# cpu.net
KiCad netlist of a schematic drawn in Altium Designer
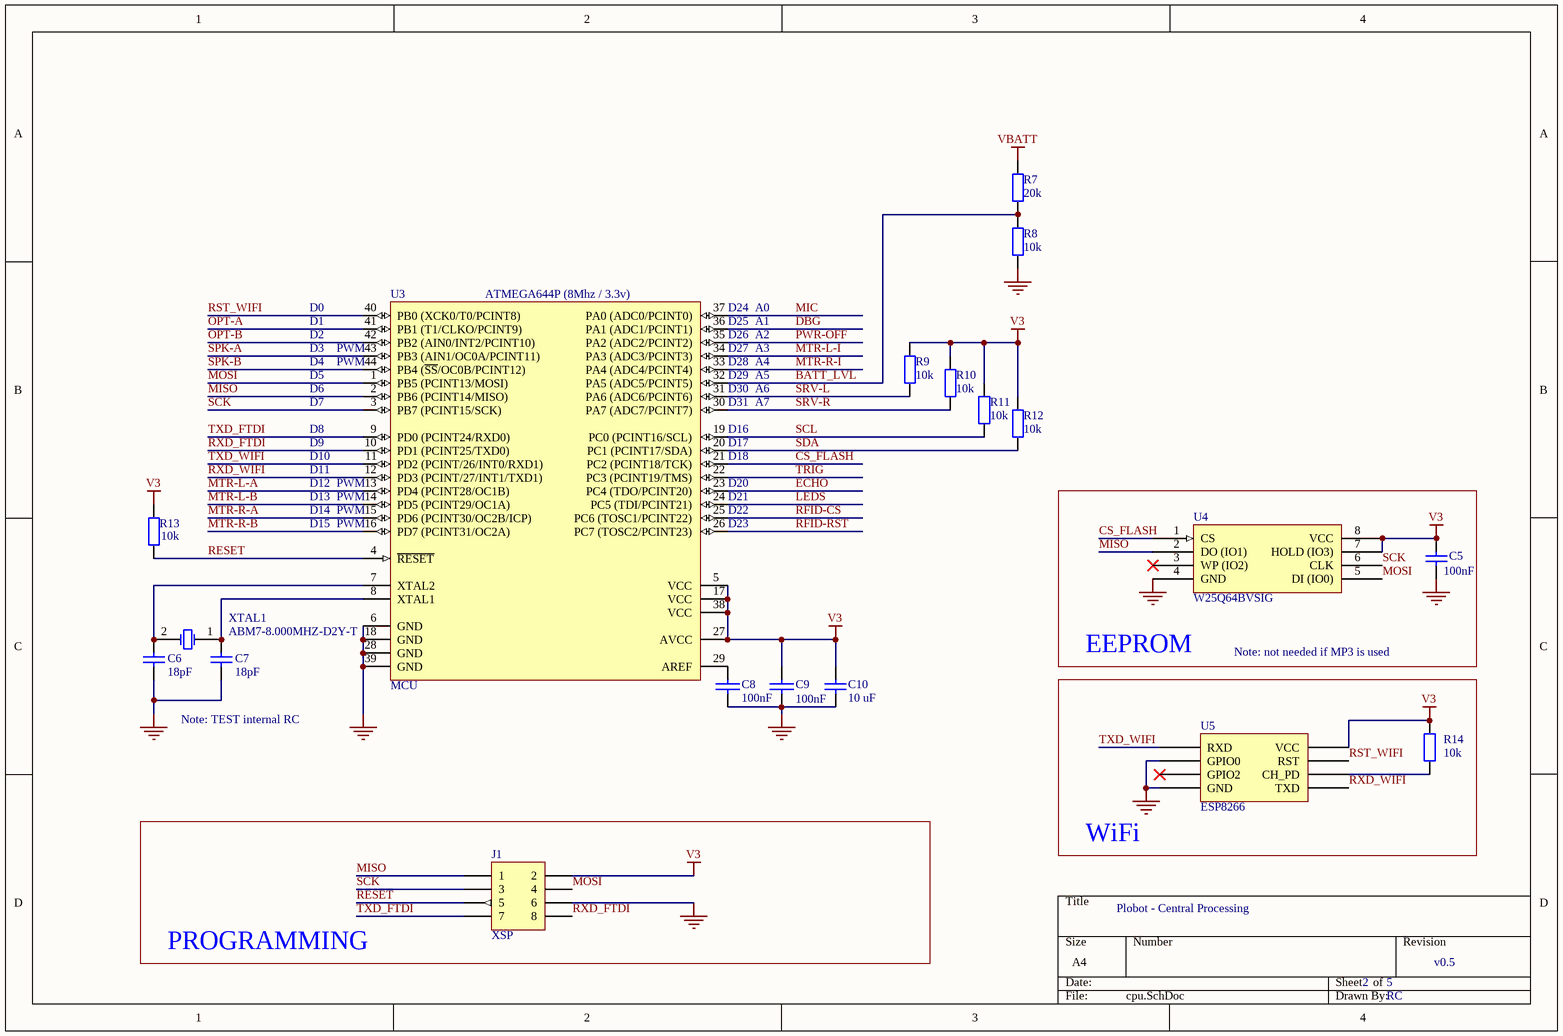
[diagram p0: cpu.SchDoc]

(export (version "E")
  (design (tool "Eeschema 10.0.6"))
  (components
    (comp (ref "C5")
      (value "100nF")
      (footprint "plobot_review:CAPC1608N")
      (description "Capacitor")
      (fields (field (name "PUBLISHER") "Altium Limited"))
      (libsource (lib "*") (part "Cap"))
    )
    (comp (ref "C6")
      (value "18pF")
      (footprint "plobot_review:CAPC1608N")
      (description "Capacitor")
      (fields (field (name "PUBLISHER") "Altium Limited"))
      (libsource (lib "*") (part "Cap"))
    )
    (comp (ref "C7")
      (value "18pF")
      (footprint "plobot_review:CAPC1608N")
      (description "Capacitor")
      (fields (field (name "PUBLISHER") "Altium Limited"))
      (libsource (lib "*") (part "Cap"))
    )
    (comp (ref "C8")
      (value "100nF")
      (footprint "plobot_review:CAPC1608N")
      (description "Capacitor")
      (libsource (lib "*") (part "CAP"))
    )
    (comp (ref "C9")
      (value "100nF")
      (footprint "plobot_review:CAPC1608N")
      (description "Capacitor")
      (libsource (lib "*") (part "CAP"))
    )
    (comp (ref "C10")
      (value "10 uF")
      (footprint "plobot_review:CAPC3216N")
      (description "Capacitor")
      (fields (field (name "PUBLISHER") "Altium Limited"))
      (libsource (lib "main_pcb") (part "Cap_2"))
    )
    (comp (ref "J1")
      (value "XSP")
      (footprint "plobot_review:HDR2X4H")
      (description "Header, 4-Pin, Dual row, Right Angle")
      (fields (field (name "PUBLISHER") "Altium Limited"))
      (libsource (lib "Miscellaneous Connectors") (part "Header 4X2H"))
    )
    (comp (ref "R7")
      (value "20k")
      (footprint "plobot_review:RESC1608N")
      (description "Resistor")
      (fields (field (name "PUBLISHER") "Altium Limited"))
      (libsource (lib "") (part "Res2_1"))
    )
    (comp (ref "R8")
      (value "10k")
      (footprint "plobot_review:RESC1608N")
      (description "Resistor")
      (fields (field (name "PUBLISHER") "Altium Limited"))
      (libsource (lib "") (part "Res2_1"))
    )
    (comp (ref "R9")
      (value "10k")
      (footprint "plobot_review:RESC1608N")
      (description "Resistor")
      (fields (field (name "PUBLISHER") "Altium Limited"))
      (libsource (lib "*") (part "Res2"))
    )
    (comp (ref "R10")
      (value "10k")
      (footprint "plobot_review:RESC1608N")
      (description "Resistor")
      (fields (field (name "PUBLISHER") "Altium Limited"))
      (libsource (lib "*") (part "Res2"))
    )
    (comp (ref "R11")
      (value "10k")
      (footprint "plobot_review:RESC1608N")
      (description "Resistor")
      (fields (field (name "PUBLISHER") "Altium Limited"))
      (libsource (lib "") (part "Res2_1"))
    )
    (comp (ref "R12")
      (value "10k")
      (footprint "plobot_review:RESC1608N")
      (description "Resistor")
      (fields (field (name "PUBLISHER") "Altium Limited"))
      (libsource (lib "*") (part "Res2"))
    )
    (comp (ref "R13")
      (value "10k")
      (footprint "plobot_review:RESC1608N")
      (description "Resistor")
      (fields (field (name "PUBLISHER") "Altium Limited"))
      (libsource (lib "*") (part "Res2"))
    )
    (comp (ref "R14")
      (value "10k")
      (footprint "plobot_review:RESC1608N")
      (description "Resistor")
      (fields (field (name "PUBLISHER") "Altium Limited"))
      (libsource (lib "") (part "Res2_2"))
    )
    (comp (ref "U3")
      (value "MCU")
      (footprint "plobot_review:atmega644p")
      (description "8-bit AVR Microcontroller, 2.7-5.5V, 20MHz, 64KB Flash, 2KB EEPROM, 4KB SRAM, 44-pin TQFP")
      (libsource (lib "*") (part "ATmega644-20AU"))
    )
    (comp (ref "U4")
      (value "W25Q64BVSIG")
      (footprint "plobot_review:W25Q64BVSIG")
      (libsource (lib "components") (part "W25Q64BVSIG"))
    )
    (comp (ref "U5")
      (value "ESP8266")
      (footprint "plobot_review:ESP8266")
      (libsource (lib "components") (part "ESP8266"))
    )
    (comp (ref "XTAL1")
      (value "ABM7-8.000MHZ-D2Y-T")
      (footprint "plobot_review:XTAL")
      (libsource (lib "components") (part "ABM7-8.000MHZ-D2Y-T"))
    )
  )
  (nets
    (net (code "1") (name "/BATT_LVL") (class "Default")
      (node (ref "R7") (pin "1") (pinfunction "1_1") (pintype "passive"))
      (node (ref "R8") (pin "2") (pinfunction "2_2") (pintype "passive"))
      (node (ref "U3") (pin "32") (pinfunction "PA5_(ADC5/PCINT5)_32") (pintype "bidirectional"))
    )
    (net (code "2") (name "/CS_FLASH") (class "Default")
      (node (ref "U3") (pin "21") (pinfunction "PC2_(PCINT18/TCK)_21") (pintype "bidirectional"))
      (node (ref "U4") (pin "1") (pinfunction "CS_1") (pintype "input"))
    )
    (net (code "3") (name "/DBG") (class "Default")
      (node (ref "U3") (pin "36") (pinfunction "PA1_(ADC1/PCINT1)_36") (pintype "bidirectional"))
    )
    (net (code "4") (name "/ECHO") (class "Default")
      (node (ref "U3") (pin "23") (pinfunction "PC4_(TDO/PCINT20)_23") (pintype "bidirectional"))
    )
    (net (code "5") (name "/LEDS") (class "Default")
      (node (ref "U3") (pin "24") (pinfunction "PC5_(TDI/PCINT21)_24") (pintype "bidirectional"))
    )
    (net (code "6") (name "/MIC") (class "Default")
      (node (ref "U3") (pin "37") (pinfunction "PA0_(ADC0/PCINT0)_37") (pintype "bidirectional"))
    )
    (net (code "7") (name "/MISO") (class "Default")
      (node (ref "J1") (pin "1") (pinfunction "1_1") (pintype "passive"))
      (node (ref "U3") (pin "2") (pinfunction "PB6_(PCINT14/MISO)_2") (pintype "bidirectional"))
      (node (ref "U4") (pin "2") (pinfunction "DO_(IO1)_2") (pintype "passive"))
    )
    (net (code "8") (name "/MOSI") (class "Default")
      (node (ref "J1") (pin "4") (pinfunction "4_4") (pintype "passive"))
      (node (ref "U3") (pin "1") (pinfunction "PB5_(PCINT13/MOSI)_1") (pintype "bidirectional"))
      (node (ref "U4") (pin "5") (pinfunction "DI_(IO0)_5") (pintype "passive"))
    )
    (net (code "9") (name "/MTR-L-A") (class "Default")
      (node (ref "U3") (pin "13") (pinfunction "PD4_(PCINT28/OC1B)_13") (pintype "bidirectional"))
    )
    (net (code "10") (name "/MTR-L-B") (class "Default")
      (node (ref "U3") (pin "14") (pinfunction "PD5_(PCINT29/OC1A)_14") (pintype "bidirectional"))
    )
    (net (code "11") (name "/MTR-L-I") (class "Default")
      (node (ref "U3") (pin "34") (pinfunction "PA3_(ADC3/PCINT3)_34") (pintype "bidirectional"))
    )
    (net (code "12") (name "/MTR-R-A") (class "Default")
      (node (ref "U3") (pin "15") (pinfunction "PD6_(PCINT30/OC2B/ICP)_15") (pintype "bidirectional"))
    )
    (net (code "13") (name "/MTR-R-B") (class "Default")
      (node (ref "U3") (pin "16") (pinfunction "PD7_(PCINT31/OC2A)_16") (pintype "bidirectional"))
    )
    (net (code "14") (name "/MTR-R-I") (class "Default")
      (node (ref "U3") (pin "33") (pinfunction "PA4_(ADC4/PCINT4)_33") (pintype "bidirectional"))
    )
    (net (code "15") (name "/OPT-A") (class "Default")
      (node (ref "U3") (pin "41") (pinfunction "PB1_(T1/CLKO/PCINT9)_41") (pintype "bidirectional"))
    )
    (net (code "16") (name "/OPT-B") (class "Default")
      (node (ref "U3") (pin "42") (pinfunction "PB2_(AIN0/INT2/PCINT10)_42") (pintype "bidirectional"))
    )
    (net (code "17") (name "/PWR-OFF") (class "Default")
      (node (ref "U3") (pin "35") (pinfunction "PA2_(ADC2/PCINT2)_35") (pintype "bidirectional"))
    )
    (net (code "18") (name "/RESET") (class "Default")
      (node (ref "J1") (pin "5") (pinfunction "5_5") (pintype "output"))
      (node (ref "R13") (pin "2") (pinfunction "2_2") (pintype "passive"))
      (node (ref "U3") (pin "4") (pinfunction "~{RESET}_4") (pintype "input"))
    )
    (net (code "19") (name "/RFID-CS") (class "Default")
      (node (ref "U3") (pin "25") (pinfunction "PC6_(TOSC1/PCINT22)_25") (pintype "bidirectional"))
    )
    (net (code "20") (name "/RFID-RST") (class "Default")
      (node (ref "U3") (pin "26") (pinfunction "PC7_(TOSC2/PCINT23)_26") (pintype "bidirectional"))
    )
    (net (code "21") (name "/RST_WIFI") (class "Default")
      (node (ref "U3") (pin "40") (pinfunction "PB0_(XCK0/T0/PCINT8)_40") (pintype "bidirectional"))
      (node (ref "U5") (pin "RST") (pinfunction "RST_RST") (pintype "passive"))
    )
    (net (code "22") (name "/RXD_FTDI") (class "Default")
      (node (ref "J1") (pin "8") (pinfunction "8_8") (pintype "passive"))
      (node (ref "U3") (pin "10") (pinfunction "PD1_(PCINT25/TXD0)_10") (pintype "bidirectional"))
    )
    (net (code "23") (name "/RXD_WIFI") (class "Default")
      (node (ref "U3") (pin "12") (pinfunction "PD3_(PCINT/27/INT1/TXD1)_12") (pintype "bidirectional"))
      (node (ref "U5") (pin "TXD") (pinfunction "TXD_TXD") (pintype "passive"))
    )
    (net (code "24") (name "/SCK") (class "Default")
      (node (ref "J1") (pin "3") (pinfunction "3_3") (pintype "passive"))
      (node (ref "U3") (pin "3") (pinfunction "PB7_(PCINT15/SCK)_3") (pintype "bidirectional"))
      (node (ref "U4") (pin "6") (pinfunction "CLK_6") (pintype "passive"))
    )
    (net (code "25") (name "/SCL") (class "Default")
      (node (ref "R11") (pin "1") (pinfunction "1_1") (pintype "passive"))
      (node (ref "U3") (pin "19") (pinfunction "PC0_(PCINT16/SCL)_19") (pintype "bidirectional"))
    )
    (net (code "26") (name "/SDA") (class "Default")
      (node (ref "R12") (pin "2") (pinfunction "2_2") (pintype "passive"))
      (node (ref "U3") (pin "20") (pinfunction "PC1_(PCINT17/SDA)_20") (pintype "bidirectional"))
    )
    (net (code "27") (name "/SPK-A") (class "Default")
      (node (ref "U3") (pin "43") (pinfunction "PB3_(AIN1/OC0A/PCINT11)_43") (pintype "bidirectional"))
    )
    (net (code "28") (name "/SPK-B") (class "Default")
      (node (ref "U3") (pin "44") (pinfunction "PB4_(~{SS}/OC0B/PCINT12)_44") (pintype "bidirectional"))
    )
    (net (code "29") (name "/SRV-L") (class "Default")
      (node (ref "R9") (pin "2") (pinfunction "2_2") (pintype "passive"))
      (node (ref "U3") (pin "31") (pinfunction "PA6_(ADC6/PCINT6)_31") (pintype "bidirectional"))
    )
    (net (code "30") (name "/SRV-R") (class "Default")
      (node (ref "R10") (pin "2") (pinfunction "2_2") (pintype "passive"))
      (node (ref "U3") (pin "30") (pinfunction "PA7_(ADC7/PCINT7)_30") (pintype "bidirectional"))
    )
    (net (code "31") (name "/TRIG") (class "Default")
      (node (ref "U3") (pin "22") (pinfunction "PC3_(PCINT19/TMS)_22") (pintype "bidirectional"))
    )
    (net (code "32") (name "/TXD_FTDI") (class "Default")
      (node (ref "J1") (pin "7") (pinfunction "7_7") (pintype "passive"))
      (node (ref "U3") (pin "9") (pinfunction "PD0_(PCINT24/RXD0)_9") (pintype "bidirectional"))
    )
    (net (code "33") (name "/TXD_WIFI") (class "Default")
      (node (ref "U3") (pin "11") (pinfunction "PD2_(PCINT/26/INT0/RXD1)_11") (pintype "bidirectional"))
      (node (ref "U5") (pin "RXD") (pinfunction "RXD_RXD") (pintype "passive"))
    )
    (net (code "34") (name "GND") (class "Default")
      (node (ref "C10") (pin "1") (pinfunction "1_1") (pintype "passive"))
      (node (ref "C5") (pin "2") (pinfunction "2_2") (pintype "passive"))
      (node (ref "C6") (pin "1") (pinfunction "1_1") (pintype "passive"))
      (node (ref "C7") (pin "1") (pinfunction "1_1") (pintype "passive"))
      (node (ref "C8") (pin "2") (pinfunction "2_2") (pintype "passive"))
      (node (ref "C9") (pin "2") (pinfunction "2_2") (pintype "passive"))
      (node (ref "J1") (pin "6") (pinfunction "6_6") (pintype "passive"))
      (node (ref "R8") (pin "1") (pinfunction "1_1") (pintype "passive"))
      (node (ref "U3") (pin "18") (pinfunction "GND_18") (pintype "power_in"))
      (node (ref "U3") (pin "28") (pinfunction "GND_28") (pintype "power_in"))
      (node (ref "U3") (pin "39") (pinfunction "GND_39") (pintype "power_in"))
      (node (ref "U3") (pin "6") (pinfunction "GND_6") (pintype "power_in"))
      (node (ref "U4") (pin "4") (pinfunction "GND_4") (pintype "power_in"))
      (node (ref "U5") (pin "GND") (pinfunction "GND_GND") (pintype "passive"))
      (node (ref "U5") (pin "GPIO0") (pinfunction "GPIO0_GPIO0") (pintype "passive"))
    )
    (net (code "35") (name "Net-(R14-Pad2)") (class "Default")
      (node (ref "R14") (pin "2") (pinfunction "2_2") (pintype "passive"))
      (node (ref "U5") (pin "CH_PD") (pinfunction "CH_PD_CH_PD") (pintype "passive"))
    )
    (net (code "36") (name "Net-(U3-AREF)") (class "Default")
      (node (ref "C8") (pin "1") (pinfunction "1_1") (pintype "passive"))
      (node (ref "U3") (pin "29") (pinfunction "AREF_29") (pintype "passive"))
    )
    (net (code "37") (name "Net-(U3-XTAL1)") (class "Default")
      (node (ref "C7") (pin "2") (pinfunction "2_2") (pintype "passive"))
      (node (ref "U3") (pin "8") (pinfunction "XTAL1_8") (pintype "passive"))
      (node (ref "XTAL1") (pin "1") (pinfunction "OSC1_1") (pintype "passive"))
    )
    (net (code "38") (name "Net-(U3-XTAL2)") (class "Default")
      (node (ref "C6") (pin "2") (pinfunction "2_2") (pintype "passive"))
      (node (ref "U3") (pin "7") (pinfunction "XTAL2_7") (pintype "passive"))
      (node (ref "XTAL1") (pin "2") (pinfunction "OSC2_2") (pintype "passive"))
    )
    (net (code "39") (name "V3") (class "Default")
      (node (ref "C10") (pin "2") (pinfunction "2_2") (pintype "passive"))
      (node (ref "C5") (pin "1") (pinfunction "1_1") (pintype "passive"))
      (node (ref "C9") (pin "1") (pinfunction "1_1") (pintype "passive"))
      (node (ref "J1") (pin "2") (pinfunction "2_2") (pintype "passive"))
      (node (ref "R10") (pin "1") (pinfunction "1_1") (pintype "passive"))
      (node (ref "R11") (pin "2") (pinfunction "2_2") (pintype "passive"))
      (node (ref "R12") (pin "1") (pinfunction "1_1") (pintype "passive"))
      (node (ref "R13") (pin "1") (pinfunction "1_1") (pintype "passive"))
      (node (ref "R14") (pin "1") (pinfunction "1_1") (pintype "passive"))
      (node (ref "R9") (pin "1") (pinfunction "1_1") (pintype "passive"))
      (node (ref "U3") (pin "17") (pinfunction "VCC_17") (pintype "power_in"))
      (node (ref "U3") (pin "27") (pinfunction "AVCC_27") (pintype "power_in"))
      (node (ref "U3") (pin "38") (pinfunction "VCC_38") (pintype "power_in"))
      (node (ref "U3") (pin "5") (pinfunction "VCC_5") (pintype "power_in"))
      (node (ref "U4") (pin "7") (pinfunction "HOLD_(IO3)_7") (pintype "passive"))
      (node (ref "U4") (pin "8") (pinfunction "VCC_8") (pintype "power_in"))
      (node (ref "U5") (pin "VCC") (pinfunction "VCC_VCC") (pintype "passive"))
    )
    (net (code "40") (name "VBATT") (class "Default")
      (node (ref "R7") (pin "2") (pinfunction "2_2") (pintype "passive"))
    )
    (net (code "41") (name "unconnected-(U4-WP_(IO2)-Pad3)") (class "Default")
      (node (ref "U4") (pin "3") (pinfunction "WP_(IO2)_3") (pintype "passive+no_connect"))
    )
    (net (code "42") (name "unconnected-(U5-PadGPIO2)") (class "Default")
      (node (ref "U5") (pin "GPIO2") (pinfunction "GPIO2_GPIO2") (pintype "passive+no_connect"))
    )
  )
)
